# Transistor.net
KiCad netlist of a schematic drawn in Altium Designer
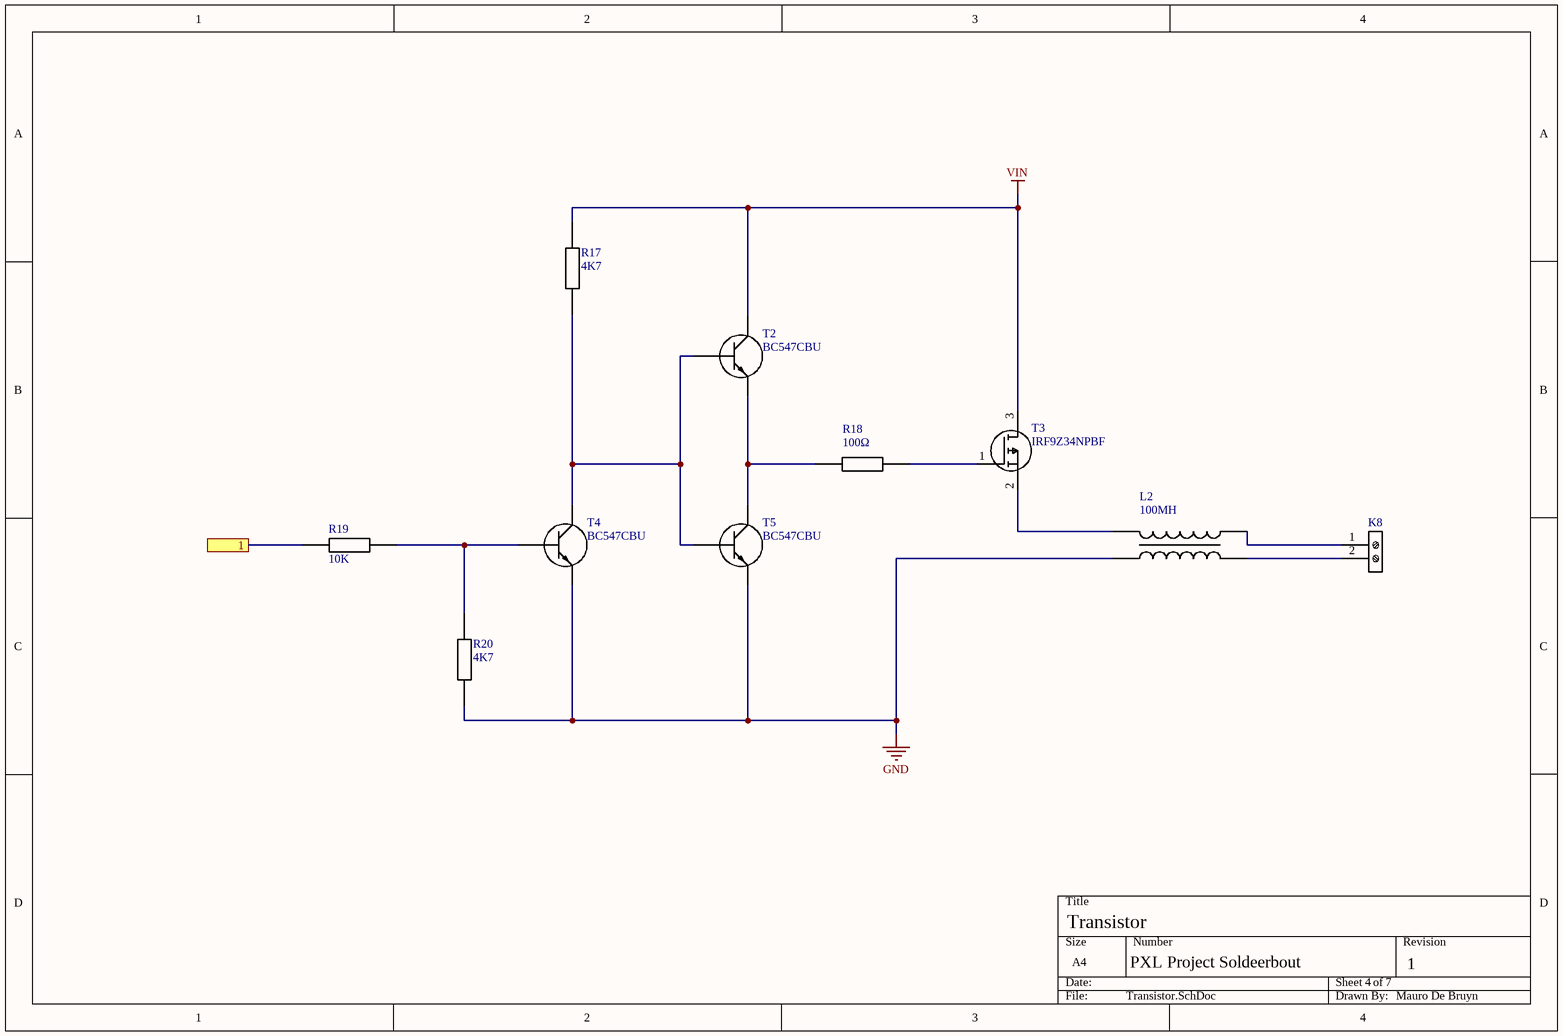
[diagram p0: Transistor.SchDoc]

(export (version "E")
  (design (tool "Eeschema 10.0.6"))
  (components
    (comp (ref "K8")
      (value "2 Pin Connector 1716020000")
      (footprint "SamacSys:1716020000")
      (description "Connector")
      (fields (field (name "MANUFACTURER_PART_NUMBER") "1716020000"))
      (libsource (lib "SamacSys") (part "2 Pin Connector 1716020000"))
    )
    (comp (ref "L2")
      (value "100MH")
      (footprint "SamacSys:CM2545X171B10")
      (description "Transformer")
      (fields (field (name "MANUFACTURER_PART_NUMBER") "CM2545X171B-10"))
      (libsource (lib "SamacSys") (part "CM2545X171B-10"))
    )
    (comp (ref "R17")
      (value "4K7")
      (footprint "SamacSys:C0805")
      (description "Resistor")
      (fields (field (name "MANUFACTURER_PART_NUMBER") "C0805C391G3GACTU"))
      (libsource (lib "SamacSys") (part "0805"))
    )
    (comp (ref "R18")
      (value "100Ω")
      (footprint "SamacSys:C0805")
      (description "Resistor")
      (fields (field (name "MANUFACTURER_PART_NUMBER") "C0805C391G3GACTU"))
      (libsource (lib "SamacSys") (part "0805"))
    )
    (comp (ref "R19")
      (value "10K")
      (footprint "SamacSys:C0805")
      (description "Resistor")
      (fields (field (name "MANUFACTURER_PART_NUMBER") "C0805C391G3GACTU"))
      (libsource (lib "SamacSys") (part "0805"))
    )
    (comp (ref "R20")
      (value "4K7")
      (footprint "SamacSys:C0805")
      (description "Resistor")
      (fields (field (name "MANUFACTURER_PART_NUMBER") "C0805C391G3GACTU"))
      (libsource (lib "SamacSys") (part "0805"))
    )
    (comp (ref "T2")
      (value "BC547CBU")
      (footprint "SamacSys:BC547CBU")
      (description "Transistor BJT NPN")
      (libsource (lib "SamacSys") (part "BC547CBU"))
    )
    (comp (ref "T3")
      (value "IRF9Z34NPBF")
      (footprint "SamacSys:TO254P469X1042X1967-3P")
      (description "MOSFET (P-Channel)")
      (fields (field (name "MOUSER2 PART NUMBER") "942-IRF9Z34NPBF"))
      (libsource (lib "SamacSys") (part "IRF9Z34NPBF"))
    )
    (comp (ref "T4")
      (value "BC547CBU")
      (footprint "SamacSys:BC547CBU")
      (description "Transistor BJT NPN")
      (libsource (lib "SamacSys") (part "BC547CBU"))
    )
    (comp (ref "T5")
      (value "BC547CBU")
      (footprint "SamacSys:BC547CBU")
      (description "Transistor BJT NPN")
      (libsource (lib "SamacSys") (part "BC547CBU"))
    )
  )
  (nets
    (net (code "1") (name "/1") (class "Default")
      (node (ref "R19") (pin "2") (pinfunction "2_2") (pintype "passive"))
    )
    (net (code "2") (name "GND") (class "Default")
      (node (ref "L2") (pin "4") (pinfunction "PRI-_4") (pintype "passive"))
      (node (ref "R20") (pin "1") (pinfunction "1_1") (pintype "passive"))
      (node (ref "T4") (pin "3") (pinfunction "E_3") (pintype "passive"))
      (node (ref "T5") (pin "3") (pinfunction "E_3") (pintype "passive"))
    )
    (net (code "3") (name "Net-(L2-PRI+)") (class "Default")
      (node (ref "L2") (pin "1") (pinfunction "PRI+_1") (pintype "passive"))
      (node (ref "T3") (pin "2") (pinfunction "S_2") (pintype "passive"))
    )
    (net (code "4") (name "Net-(L2-SEC+)") (class "Default")
      (node (ref "K8") (pin "1") (pinfunction "1_1") (pintype "passive"))
      (node (ref "L2") (pin "2") (pinfunction "SEC+_2") (pintype "passive"))
    )
    (net (code "5") (name "Net-(L2-SEC-)") (class "Default")
      (node (ref "K8") (pin "2") (pinfunction "2_2") (pintype "passive"))
      (node (ref "L2") (pin "3") (pinfunction "SEC-_3") (pintype "passive"))
    )
    (net (code "6") (name "Net-(T2-B)") (class "Default")
      (node (ref "R17") (pin "1") (pinfunction "1_1") (pintype "passive"))
      (node (ref "T2") (pin "2") (pinfunction "B_2") (pintype "passive"))
      (node (ref "T4") (pin "1") (pinfunction "C_1") (pintype "passive"))
      (node (ref "T5") (pin "2") (pinfunction "B_2") (pintype "passive"))
    )
    (net (code "7") (name "Net-(T2-E)") (class "Default")
      (node (ref "R18") (pin "1") (pinfunction "1_1") (pintype "passive"))
      (node (ref "T2") (pin "3") (pinfunction "E_3") (pintype "passive"))
      (node (ref "T5") (pin "1") (pinfunction "C_1") (pintype "passive"))
    )
    (net (code "8") (name "Net-(T3-G)") (class "Default")
      (node (ref "R18") (pin "2") (pinfunction "2_2") (pintype "passive"))
      (node (ref "T3") (pin "1") (pinfunction "G_1") (pintype "passive"))
    )
    (net (code "9") (name "Net-(T4-B)") (class "Default")
      (node (ref "R19") (pin "1") (pinfunction "1_1") (pintype "passive"))
      (node (ref "R20") (pin "2") (pinfunction "2_2") (pintype "passive"))
      (node (ref "T4") (pin "2") (pinfunction "B_2") (pintype "passive"))
    )
    (net (code "10") (name "VIN") (class "Default")
      (node (ref "R17") (pin "2") (pinfunction "2_2") (pintype "passive"))
      (node (ref "T2") (pin "1") (pinfunction "C_1") (pintype "passive"))
      (node (ref "T3") (pin "3") (pinfunction "D_3") (pintype "passive"))
    )
  )
)
